# PowerAndSystem.net
KiCad netlist of a schematic drawn in Altium Designer
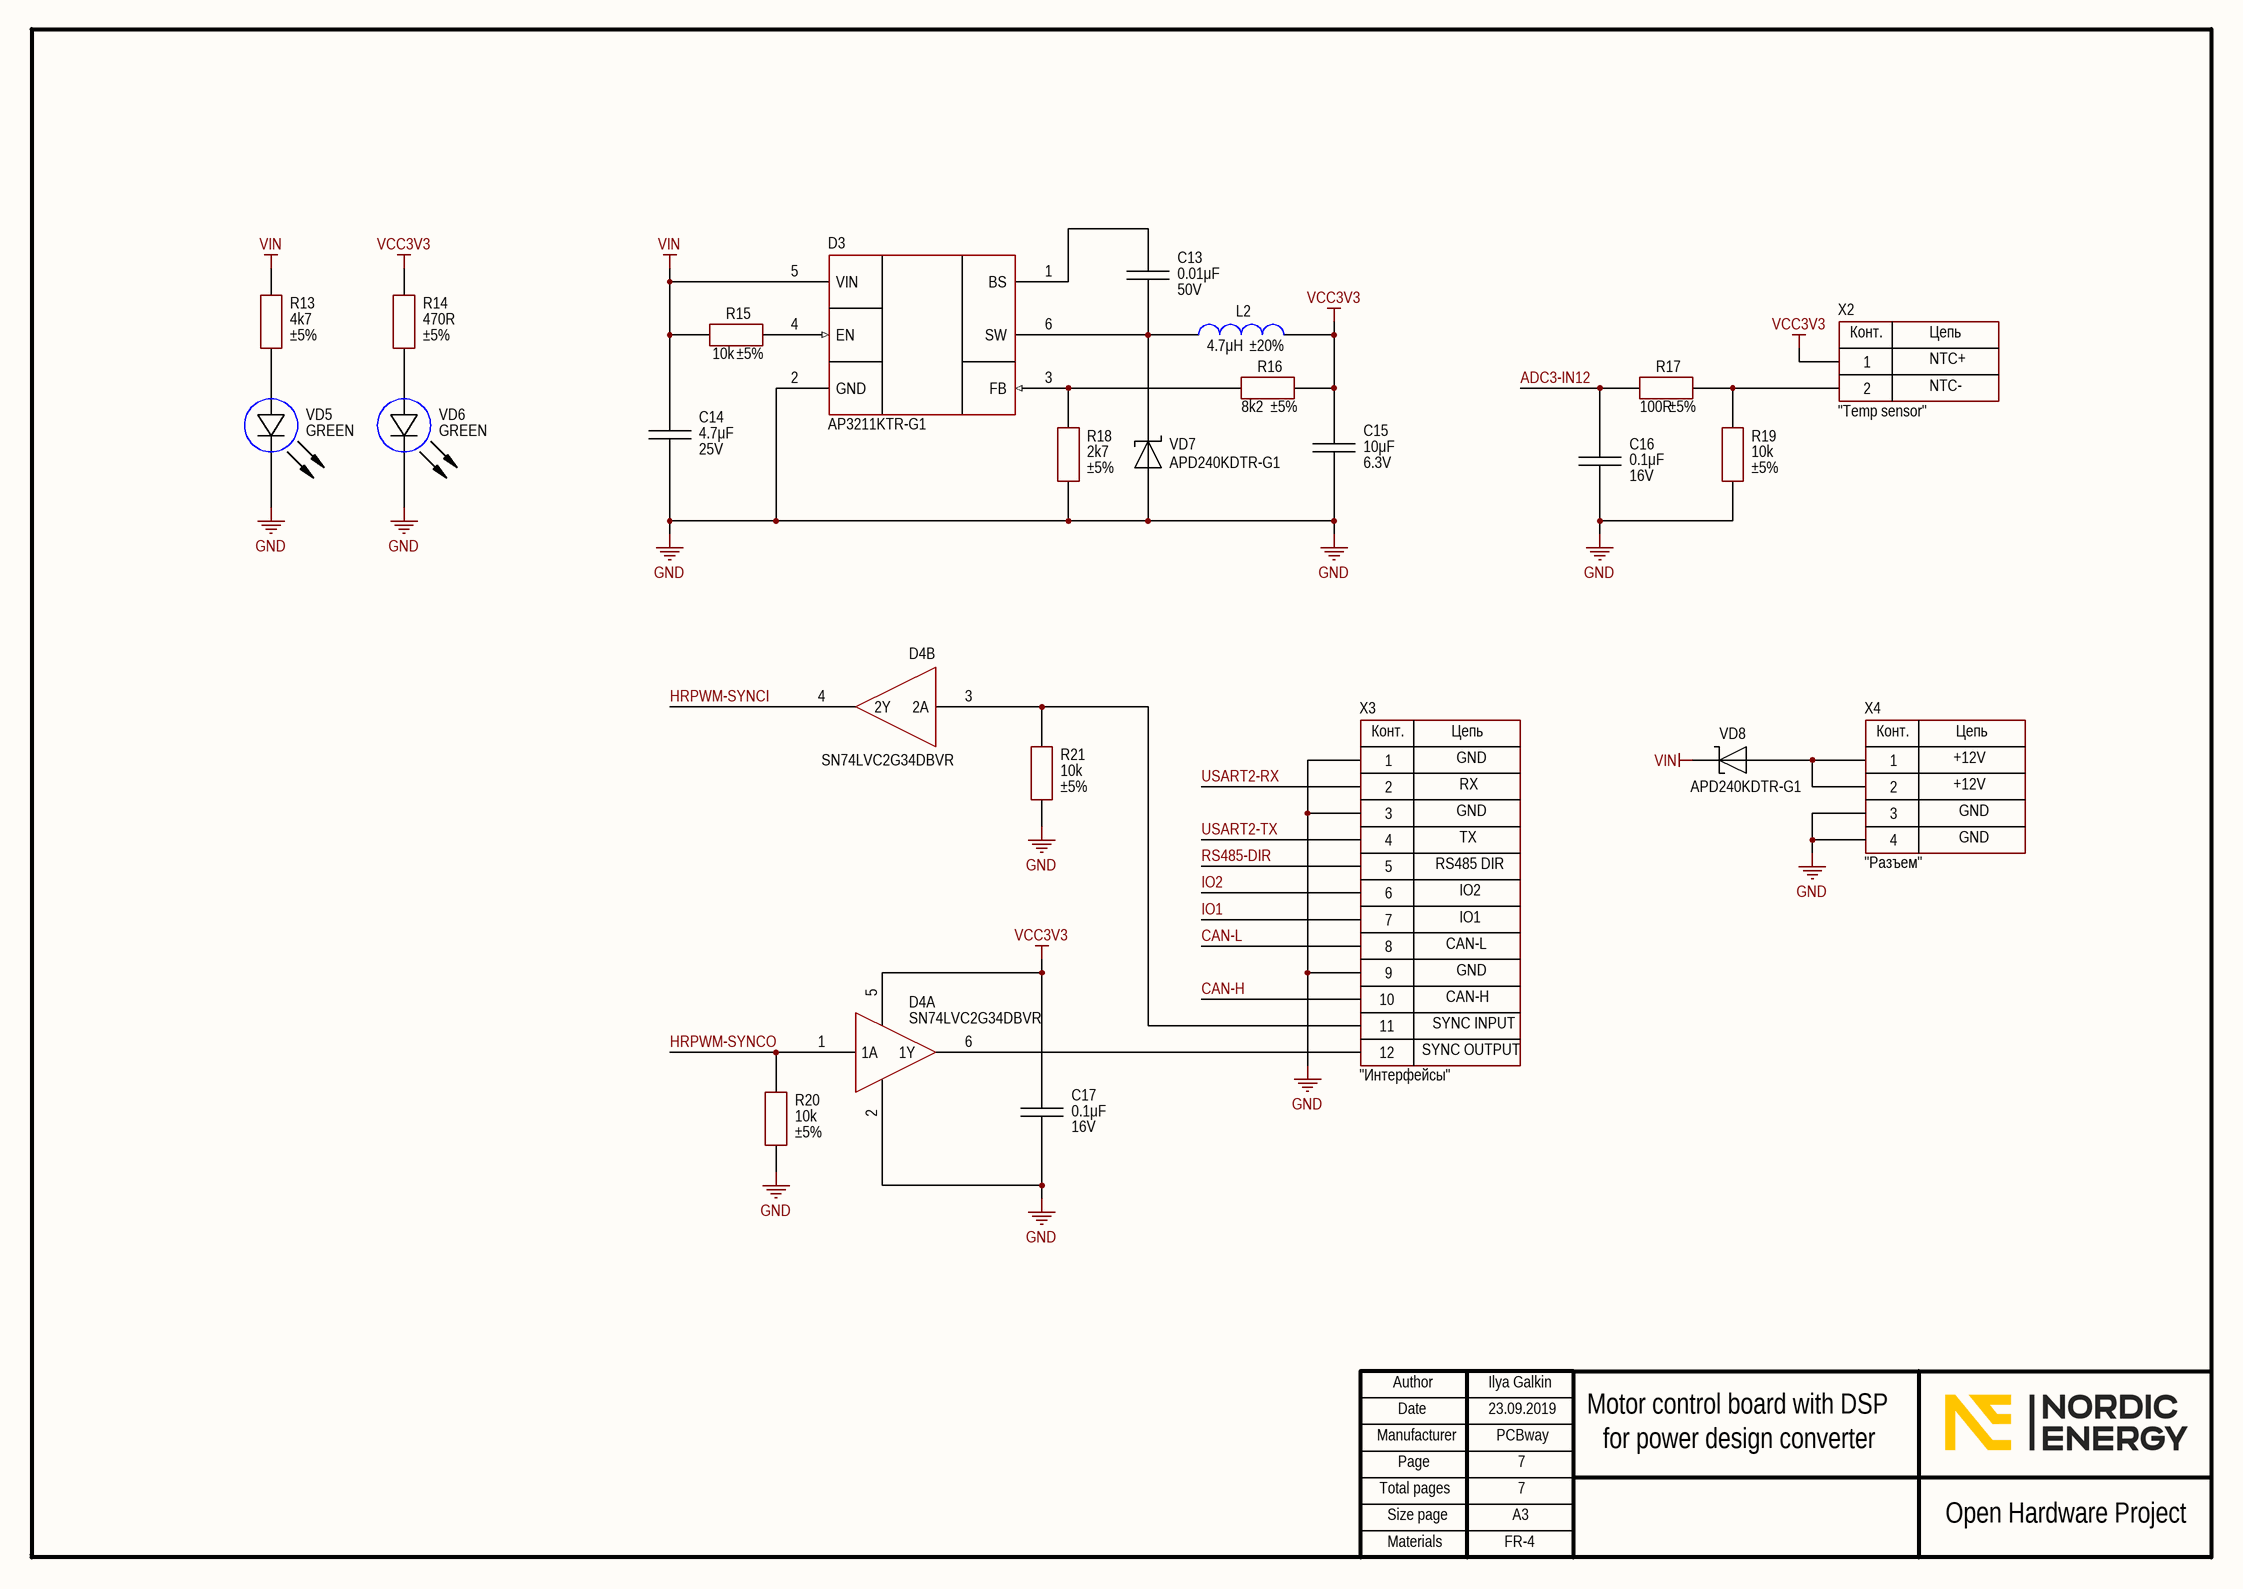
[diagram p0: PowerAndSystem.SchDoc]

(export (version "E")
  (design (tool "Eeschema 10.0.6"))
  (components
    (comp (ref "C13")
      (value "0.01μF")
      (footprint "CAP: 0805")
      (fields
        (field (name "MANUFACTURER") "Yageo")
        (field (name "PARTNUMBER") "CC0805KRX7R9BB103")
        (field (name "VALUEMANUFACTURERPARTNUMBER") "Ceramic capacitor, 0.01μF, X7R, ±10%, 50V, 0805, -55...+125°C")
        (field (name "VOLTAGE") "50V")
      )
      (libsource (lib "Capacitor") (part "Ceramic_0805"))
    )
    (comp (ref "C14")
      (value "4.7μF")
      (footprint "CAP: 0805")
      (fields
        (field (name "MANUFACTURER") "Samsung")
        (field (name "PARTNUMBER") "CL21B475KAFNNNE")
        (field (name "VALUEMANUFACTURERPARTNUMBER") "Ceramic capacitor, 4.7μF, X7R, ±10%, 25V, 0805, -55...+125°C")
        (field (name "VOLTAGE") "25V")
      )
      (libsource (lib "Capacitor") (part "Ceramic_0805"))
    )
    (comp (ref "C15")
      (value "10μF")
      (footprint "CAP: 0805")
      (fields
        (field (name "MANUFACTURER") "Samsung")
        (field (name "PARTNUMBER") "CL21B106KQQNNNE")
        (field (name "VALUEMANUFACTURERPARTNUMBER") "Ceramic capacitor, 10μF, X7R, ±10%, 6.3V, 0805, -55...+125°C")
        (field (name "VOLTAGE") "6.3V")
      )
      (libsource (lib "Capacitor") (part "Ceramic_0805"))
    )
    (comp (ref "C16")
      (value "0.1μF")
      (footprint "CAP: 0805")
      (fields
        (field (name "MANUFACTURER") "Yageo")
        (field (name "PARTNUMBER") "CC0805KRX7R7BB104")
        (field (name "VALUEMANUFACTURERPARTNUMBER") "Ceramic capacitor, 0.1μF, X7R, ±10%, 16V, 0805, -55...+125°C")
        (field (name "VOLTAGE") "16V")
      )
      (libsource (lib "Capacitor") (part "Ceramic_0805"))
    )
    (comp (ref "C17")
      (value "0.1μF")
      (footprint "CAP: 0805")
      (fields
        (field (name "MANUFACTURER") "Yageo")
        (field (name "PARTNUMBER") "CC0805KRX7R7BB104")
        (field (name "VALUEMANUFACTURERPARTNUMBER") "Ceramic capacitor, 0.1μF, X7R, ±10%, 16V, 0805, -55...+125°C")
        (field (name "VOLTAGE") "16V")
      )
      (libsource (lib "Capacitor") (part "Ceramic_0805"))
    )
    (comp (ref "D3")
      (value "~")
      (footprint "SOT23-6")
      (description "Buck converter")
      (fields
        (field (name "MANUFACTURER") "Diodes Incorporated")
        (field (name "VALUEMANUFACTURERPARTNUMBER") "DC/DC buck converter, input 4.5...18V, 1.4MHz, output 0.81...15V, 1.5A, -40...+85°C, SOT23-6")
        (field (name "PARTNUMBER") "AP3211KTR-G1")
      )
      (libsource (lib "IC. Power supply") (part "AP3211KTR-G1"))
    )
    (comp (ref "D4")
      (value "~")
      (footprint "SOT23-6")
      (description "Buffer")
      (fields
        (field (name "MANUFACTURER") "Texas Instruments")
        (field (name "VALUEMANUFACTURERPARTNUMBER") "IC logic buffer, 1.65...5.5V, -40...+125°C, SOT23-6")
        (field (name "PARTNUMBER") "SN74LVC2G34DBVR")
      )
      (libsource (lib "IC. Logic") (part "SN74LVC2G34DBVR"))
    )
    (comp (ref "L2")
      (value "4.7μH")
      (footprint "IND: SRP2510A")
      (fields
        (field (name "MANUFACTURER") "Bourns")
        (field (name "PARTNUMBER") "SRP2510A-4R7M")
        (field (name "VALUEMANUFACTURERPARTNUMBER") "Fixed inductor, 4.7μH, ±20%, SRP2510A, 1.36A, -40...+125°C")
        (field (name "TOLERANCE") "±20%")
      )
      (libsource (lib "Inductor") (part "Inductor_SRP2510A"))
    )
    (comp (ref "R13")
      (value "4k7")
      (footprint "RES: 0805")
      (fields
        (field (name "MANUFACTURER") "Yageo")
        (field (name "PARTNUMBER") "RC0805JR-074K7L")
        (field (name "VALUEMANUFACTURERPARTNUMBER") "Resistor film, 4k7, ±5%, 0805, 0.125W, -55...+125°C")
        (field (name "TOLERANCE") "±5%")
      )
      (libsource (lib "Resistor") (part "Resistor_0805"))
    )
    (comp (ref "R14")
      (value "470R")
      (footprint "RES: 0805")
      (fields
        (field (name "MANUFACTURER") "Yageo")
        (field (name "PARTNUMBER") "RC0805JR-07470RL")
        (field (name "VALUEMANUFACTURERPARTNUMBER") "Resistor film, 470R, ±5%, 0805, 0.125W, -55...+125°C")
        (field (name "TOLERANCE") "±5%")
      )
      (libsource (lib "") (part "Resistor_0805_2"))
    )
    (comp (ref "R15")
      (value "10k")
      (footprint "RES: 0805")
      (fields
        (field (name "MANUFACTURER") "Yageo")
        (field (name "PARTNUMBER") "RC0805JR-0710KL")
        (field (name "VALUEMANUFACTURERPARTNUMBER") "Resistor film, 10k, ±5%, 0805, 0.125W, -55...+125°C")
        (field (name "TOLERANCE") "±5%")
      )
      (libsource (lib "") (part "Resistor_0805_1"))
    )
    (comp (ref "R16")
      (value "8k2")
      (footprint "RES: 0805")
      (fields
        (field (name "MANUFACTURER") "Yageo")
        (field (name "PARTNUMBER") "RC0805JR-078K2L")
        (field (name "VALUEMANUFACTURERPARTNUMBER") "Resistor film, 8k2, ±5%, 0805, 0.125W, -55...+125°C")
        (field (name "TOLERANCE") "±5%")
      )
      (libsource (lib "") (part "Resistor_0805_1"))
    )
    (comp (ref "R17")
      (value "100R")
      (footprint "RES: 0805")
      (fields
        (field (name "MANUFACTURER") "Yageo")
        (field (name "PARTNUMBER") "RC0805JR-07100RL")
        (field (name "VALUEMANUFACTURERPARTNUMBER") "Resistor film, 100R, ±5%, 0805, 0.125W, -55...+125°C")
        (field (name "TOLERANCE") "±5%")
      )
      (libsource (lib "") (part "Resistor_0805_1"))
    )
    (comp (ref "R18")
      (value "2k7")
      (footprint "RES: 0805")
      (fields
        (field (name "MANUFACTURER") "Yageo")
        (field (name "PARTNUMBER") "RC0805JR-072K7L")
        (field (name "VALUEMANUFACTURERPARTNUMBER") "Resistor film, 2k7, ±5%, 0805, 0.125W, -55...+125°C")
        (field (name "TOLERANCE") "±5%")
      )
      (libsource (lib "") (part "Resistor_0805_2"))
    )
    (comp (ref "R19")
      (value "10k")
      (footprint "RES: 0805")
      (fields
        (field (name "MANUFACTURER") "Yageo")
        (field (name "PARTNUMBER") "RC0805JR-0710KL")
        (field (name "VALUEMANUFACTURERPARTNUMBER") "Resistor film, 10k, ±5%, 0805, 0.125W, -55...+125°C")
        (field (name "TOLERANCE") "±5%")
      )
      (libsource (lib "") (part "Resistor_0805_2"))
    )
    (comp (ref "R20")
      (value "10k")
      (footprint "RES: 0805")
      (fields
        (field (name "MANUFACTURER") "Yageo")
        (field (name "PARTNUMBER") "RC0805JR-0710KL")
        (field (name "VALUEMANUFACTURERPARTNUMBER") "Resistor film, 10k, ±5%, 0805, 0.125W, -55...+125°C")
        (field (name "TOLERANCE") "±5%")
      )
      (libsource (lib "Resistor") (part "Resistor_0805"))
    )
    (comp (ref "R21")
      (value "10k")
      (footprint "RES: 0805")
      (fields
        (field (name "MANUFACTURER") "Yageo")
        (field (name "PARTNUMBER") "RC0805JR-0710KL")
        (field (name "VALUEMANUFACTURERPARTNUMBER") "Resistor film, 10k, ±5%, 0805, 0.125W, -55...+125°C")
        (field (name "TOLERANCE") "±5%")
      )
      (libsource (lib "Resistor") (part "Resistor_0805"))
    )
    (comp (ref "VD5")
      (value "~")
      (footprint "LED: 0805G")
      (fields
        (field (name "MANUFACTURER") "Wurth")
        (field (name "VALUEMANUFACTURERPARTNUMBER") "LED, 20mA, 2V, 0805, -55...+150°C")
        (field (name "PARTNUMBER") "150080VS75000")
        (field (name "COLOR") "GREEN")
      )
      (libsource (lib "Diode") (part "LED_single"))
    )
    (comp (ref "VD6")
      (value "~")
      (footprint "LED: 0805G")
      (fields
        (field (name "MANUFACTURER") "Wurth")
        (field (name "VALUEMANUFACTURERPARTNUMBER") "LED, 20mA, 2V, 0805, -55...+150°C")
        (field (name "PARTNUMBER") "150080VS75000")
        (field (name "COLOR") "GREEN")
      )
      (libsource (lib "Diode") (part "LED_single"))
    )
    (comp (ref "VD7")
      (value "~")
      (footprint "DIODE: SOD123")
      (fields
        (field (name "MANUFACTURER") "Diodes Incorporated")
        (field (name "VALUEMANUFACTURERPARTNUMBER") "Schottky diode, 40V, 2A, 500mV, 15pF, SOD-123, -55...+150°C")
        (field (name "VOLTAGE") "40V")
        (field (name "PARTNUMBER") "APD240KDTR-G1")
      )
      (libsource (lib "Diode") (part "Schottky_single"))
    )
    (comp (ref "VD8")
      (value "~")
      (footprint "DIODE: SOD123")
      (fields
        (field (name "MANUFACTURER") "Diodes Incorporated")
        (field (name "VALUEMANUFACTURERPARTNUMBER") "Schottky diode, 40V, 2A, 500mV, 15pF, SOD-123, -55...+150°C")
        (field (name "VOLTAGE") "40V")
        (field (name "PARTNUMBER") "APD240KDTR-G1")
      )
      (libsource (lib "Diode") (part "Schottky_single"))
    )
    (comp (ref "X2")
      (value "~")
      (footprint "CON: PLS-2")
      (fields
        (field (name "MANUFACTURER") "Connfly")
        (field (name "VALUEMANUFACTURERPARTNUMBER") "Connector, 2pin, 2.54mm, 500VAC, 3A")
        (field (name "PARTNUMBER") "PLS-2")
        (field (name "COMMENTTEXT") "\"Temp sensor\"")
      )
      (libsource (lib "Connector") (part "PLS-2"))
    )
    (comp (ref "X3")
      (value "~")
      (footprint "CON: PLD-12")
      (fields
        (field (name "MANUFACTURER") "Connfly")
        (field (name "VALUEMANUFACTURERPARTNUMBER") "Connector, 12pin, 2.54mm, 500VAC, 3A")
        (field (name "PARTNUMBER") "PLD-12")
        (field (name "COMMENTTEXT") "\"Интерфейсы\"")
      )
      (libsource (lib "Connector") (part "PLD-12"))
    )
    (comp (ref "X4")
      (value "~")
      (footprint "CON: PLD-4")
      (fields
        (field (name "MANUFACTURER") "Connfly")
        (field (name "VALUEMANUFACTURERPARTNUMBER") "Connector, 6pin, 2.54mm, 500VAC, 3A")
        (field (name "PARTNUMBER") "PLD-4")
        (field (name "COMMENTTEXT") "\"Разъем\"")
      )
      (libsource (lib "Connector") (part "PLD-4"))
    )
  )
  (nets
    (net (code "1") (name "/ADC3-IN12") (class "Default")
      (node (ref "C16") (pin "2") (pinfunction "2_2") (pintype "power_in"))
      (node (ref "R17") (pin "1") (pinfunction "1_1") (pintype "passive"))
    )
    (net (code "2") (name "/CAN-H") (class "Default")
      (node (ref "X3") (pin "10") (pinfunction "10_10") (pintype "power_in"))
    )
    (net (code "3") (name "/CAN-L") (class "Default")
      (node (ref "X3") (pin "8") (pinfunction "8_8") (pintype "power_in"))
    )
    (net (code "4") (name "/HRPWM-SYNCI") (class "Default")
      (node (ref "D4") (pin "4") (pinfunction "2Y_4") (pintype "passive"))
    )
    (net (code "5") (name "/HRPWM-SYNCO") (class "Default")
      (node (ref "D4") (pin "1") (pinfunction "1A_1") (pintype "passive"))
      (node (ref "R20") (pin "1") (pinfunction "1_1") (pintype "passive"))
    )
    (net (code "6") (name "/IO1") (class "Default")
      (node (ref "X3") (pin "7") (pinfunction "7_7") (pintype "power_in"))
    )
    (net (code "7") (name "/IO2") (class "Default")
      (node (ref "X3") (pin "6") (pinfunction "6_6") (pintype "power_in"))
    )
    (net (code "8") (name "/RS485-DIR") (class "Default")
      (node (ref "X3") (pin "5") (pinfunction "5_5") (pintype "power_in"))
    )
    (net (code "9") (name "/USART2-RX") (class "Default")
      (node (ref "X3") (pin "2") (pinfunction "2_2") (pintype "passive"))
    )
    (net (code "10") (name "/USART2-TX") (class "Default")
      (node (ref "X3") (pin "4") (pinfunction "4_4") (pintype "power_in"))
    )
    (net (code "11") (name "GND") (class "Default")
      (node (ref "C14") (pin "1") (pinfunction "1_1") (pintype "power_in"))
      (node (ref "C15") (pin "1") (pinfunction "1_1") (pintype "power_in"))
      (node (ref "C16") (pin "1") (pinfunction "1_1") (pintype "power_in"))
      (node (ref "C17") (pin "1") (pinfunction "1_1") (pintype "power_in"))
      (node (ref "D3") (pin "2") (pinfunction "GND_2") (pintype "passive"))
      (node (ref "D4") (pin "2") (pintype "passive"))
      (node (ref "R18") (pin "1") (pinfunction "1_1") (pintype "passive"))
      (node (ref "R19") (pin "1") (pinfunction "1_1") (pintype "passive"))
      (node (ref "R20") (pin "2") (pinfunction "2_2") (pintype "passive"))
      (node (ref "R21") (pin "2") (pinfunction "2_2") (pintype "passive"))
      (node (ref "VD5") (pin "2") (pinfunction "C_2") (pintype "passive"))
      (node (ref "VD6") (pin "2") (pinfunction "C_2") (pintype "passive"))
      (node (ref "VD7") (pin "1") (pinfunction "1_1") (pintype "passive"))
      (node (ref "X3") (pin "1") (pinfunction "1_1") (pintype "passive"))
      (node (ref "X3") (pin "3") (pinfunction "3_3") (pintype "power_in"))
      (node (ref "X3") (pin "9") (pinfunction "9_9") (pintype "power_in"))
      (node (ref "X4") (pin "3") (pinfunction "3_3") (pintype "power_in"))
      (node (ref "X4") (pin "4") (pinfunction "4_4") (pintype "power_in"))
    )
    (net (code "12") (name "Net-(D3-BS)") (class "Default")
      (node (ref "C13") (pin "2") (pinfunction "2_2") (pintype "power_in"))
      (node (ref "D3") (pin "1") (pinfunction "BS_1") (pintype "passive"))
    )
    (net (code "13") (name "Net-(D3-EN)") (class "Default")
      (node (ref "D3") (pin "4") (pinfunction "EN_4") (pintype "input"))
      (node (ref "R15") (pin "2") (pinfunction "2_2") (pintype "passive"))
    )
    (net (code "14") (name "Net-(D3-FB)") (class "Default")
      (node (ref "D3") (pin "3") (pinfunction "FB_3") (pintype "input"))
      (node (ref "R16") (pin "1") (pinfunction "1_1") (pintype "passive"))
      (node (ref "R18") (pin "2") (pinfunction "2_2") (pintype "passive"))
    )
    (net (code "15") (name "Net-(D3-SW)") (class "Default")
      (node (ref "C13") (pin "1") (pinfunction "1_1") (pintype "power_in"))
      (node (ref "D3") (pin "6") (pinfunction "SW_6") (pintype "passive"))
      (node (ref "L2") (pin "2") (pinfunction "2_2") (pintype "passive"))
      (node (ref "VD7") (pin "2") (pinfunction "2_2") (pintype "passive"))
    )
    (net (code "16") (name "Net-(D4A-1Y)") (class "Default")
      (node (ref "D4") (pin "6") (pinfunction "1Y_6") (pintype "passive"))
      (node (ref "X3") (pin "12") (pinfunction "12_12") (pintype "power_in"))
    )
    (net (code "17") (name "Net-(D4B-2A)") (class "Default")
      (node (ref "D4") (pin "3") (pinfunction "2A_3") (pintype "passive"))
      (node (ref "R21") (pin "1") (pinfunction "1_1") (pintype "passive"))
      (node (ref "X3") (pin "11") (pinfunction "11_11") (pintype "power_in"))
    )
    (net (code "18") (name "Net-(R17-Pad2)") (class "Default")
      (node (ref "R17") (pin "2") (pinfunction "2_2") (pintype "passive"))
      (node (ref "R19") (pin "2") (pinfunction "2_2") (pintype "passive"))
      (node (ref "X2") (pin "2") (pinfunction "2_2") (pintype "passive"))
    )
    (net (code "19") (name "Net-(VD5-A)") (class "Default")
      (node (ref "R13") (pin "2") (pinfunction "2_2") (pintype "passive"))
      (node (ref "VD5") (pin "1") (pinfunction "A_1") (pintype "passive"))
    )
    (net (code "20") (name "Net-(VD6-A)") (class "Default")
      (node (ref "R14") (pin "1") (pinfunction "1_1") (pintype "passive"))
      (node (ref "VD6") (pin "1") (pinfunction "A_1") (pintype "passive"))
    )
    (net (code "21") (name "Net-(VD8-Pad1)") (class "Default")
      (node (ref "VD8") (pin "1") (pinfunction "1_1") (pintype "passive"))
      (node (ref "X4") (pin "1") (pinfunction "1_1") (pintype "passive"))
      (node (ref "X4") (pin "2") (pinfunction "2_2") (pintype "passive"))
    )
    (net (code "22") (name "VCC3V3") (class "Default")
      (node (ref "C15") (pin "2") (pinfunction "2_2") (pintype "power_in"))
      (node (ref "C17") (pin "2") (pinfunction "2_2") (pintype "power_in"))
      (node (ref "D4") (pin "5") (pintype "passive"))
      (node (ref "L2") (pin "1") (pinfunction "1_1") (pintype "passive"))
      (node (ref "R14") (pin "2") (pinfunction "2_2") (pintype "passive"))
      (node (ref "R16") (pin "2") (pinfunction "2_2") (pintype "passive"))
      (node (ref "X2") (pin "1") (pinfunction "1_1") (pintype "passive"))
    )
    (net (code "23") (name "VIN") (class "Default")
      (node (ref "C14") (pin "2") (pinfunction "2_2") (pintype "power_in"))
      (node (ref "D3") (pin "5") (pinfunction "VIN_5") (pintype "passive"))
      (node (ref "R13") (pin "1") (pinfunction "1_1") (pintype "passive"))
      (node (ref "R15") (pin "1") (pinfunction "1_1") (pintype "passive"))
      (node (ref "VD8") (pin "2") (pinfunction "2_2") (pintype "passive"))
    )
  )
)
